# 1_Sheet_1.net
KiCad netlist of a schematic drawn in Altium Designer
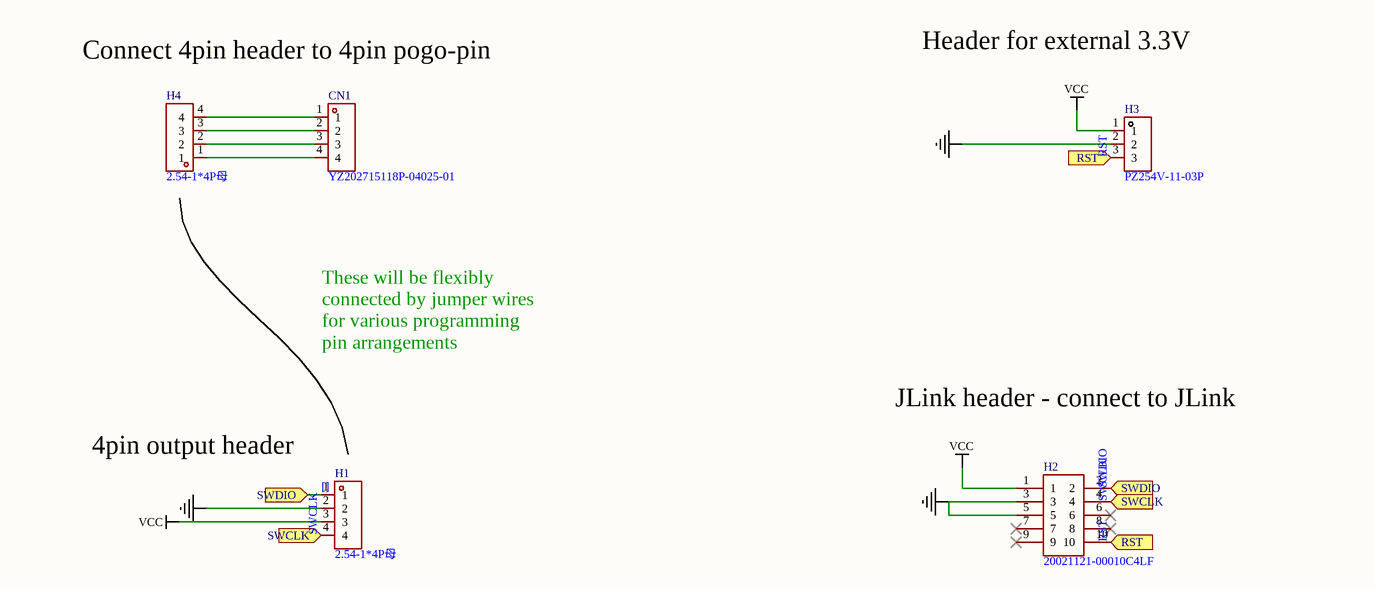
[diagram p0: 1_Sheet_1.schdoc]

(export (version "E")
  (design (tool "Eeschema 10.0.6"))
  (components
    (comp (ref "CN1")
      (value "YZ202715118P-04025-01")
      (footprint "BAT-TH_4P-P2.50_YZ202715118P-04025-01")
      (fields (field (name "MANUFACTURER") "Xinyangze(鑫扬泽)"))
      (libsource (lib "altium-import") (part "root_0_YZ202715118P-04025-01_"))
    )
    (comp (ref "H1")
      (value "2.54-1*4P母")
      (footprint "HDR-TH_4P-P2.54-V-F")
      (fields (field (name "MANUFACTURER") "BOOMELE(博穆精密)"))
      (libsource (lib "altium-import") (part "root_0_2.54-1*4P母_"))
    )
    (comp (ref "H2")
      (value "20021121-00010C4LF")
      (footprint "HDR-SMD_10P-P1.27-V-M-R2-C5-S1.27-LS5.5")
      (fields (field (name "MANUFACTURER") "Amphenol"))
      (libsource (lib "altium-import") (part "root_3_20021121-00010C4LF_"))
    )
    (comp (ref "H3")
      (value "PZ254V-11-03P")
      (footprint "HDR-TH_3P-P2.54-V-M")
      (fields (field (name "MANUFACTURER") "XFCN(兴飞)"))
      (libsource (lib "altium-import") (part "root_0_PZ254V-11-03P_"))
    )
    (comp (ref "H4")
      (value "2.54-1*4P母")
      (footprint "HDR-TH_4P-P2.54-V-F")
      (fields (field (name "MANUFACTURER") "BOOMELE(博穆精密)"))
      (libsource (lib "altium-import") (part "root_2_2.54-1*4P母_"))
    )
  )
  (nets
    (net (code "1") (name "/RST") (class "Default")
      (node (ref "H2") (pin "10") (pinfunction "10_10") (pintype "passive"))
      (node (ref "H3") (pin "3") (pinfunction "3_3") (pintype "passive"))
    )
    (net (code "2") (name "/SWCLK") (class "Default")
      (node (ref "H1") (pin "4") (pinfunction "4_4") (pintype "passive"))
      (node (ref "H2") (pin "4") (pinfunction "4_4") (pintype "passive"))
    )
    (net (code "3") (name "/SWDIO") (class "Default")
      (node (ref "H1") (pin "1") (pinfunction "1_1") (pintype "passive"))
      (node (ref "H2") (pin "2") (pinfunction "2_2") (pintype "passive"))
    )
    (net (code "4") (name "GND") (class "Default")
      (node (ref "H1") (pin "2") (pinfunction "2_2") (pintype "passive"))
      (node (ref "H2") (pin "3") (pinfunction "3_3") (pintype "passive"))
      (node (ref "H2") (pin "5") (pinfunction "5_5") (pintype "passive"))
      (node (ref "H3") (pin "2") (pinfunction "2_2") (pintype "passive"))
    )
    (net (code "5") (name "Net-(CN1-Pad1)") (class "Default")
      (node (ref "CN1") (pin "1") (pinfunction "1_1") (pintype "passive"))
      (node (ref "H4") (pin "4") (pinfunction "4_4") (pintype "passive"))
    )
    (net (code "6") (name "Net-(CN1-Pad2)") (class "Default")
      (node (ref "CN1") (pin "2") (pinfunction "2_2") (pintype "passive"))
      (node (ref "H4") (pin "3") (pinfunction "3_3") (pintype "passive"))
    )
    (net (code "7") (name "Net-(CN1-Pad3)") (class "Default")
      (node (ref "CN1") (pin "3") (pinfunction "3_3") (pintype "passive"))
      (node (ref "H4") (pin "2") (pinfunction "2_2") (pintype "passive"))
    )
    (net (code "8") (name "Net-(CN1-Pad4)") (class "Default")
      (node (ref "CN1") (pin "4") (pinfunction "4_4") (pintype "passive"))
      (node (ref "H4") (pin "1") (pinfunction "1_1") (pintype "passive"))
    )
    (net (code "9") (name "VCC") (class "Default")
      (node (ref "H1") (pin "3") (pinfunction "3_3") (pintype "passive"))
      (node (ref "H2") (pin "1") (pinfunction "1_1") (pintype "passive"))
      (node (ref "H3") (pin "1") (pinfunction "1_1") (pintype "passive"))
    )
    (net (code "10") (name "unconnected-(H2-Pad6)") (class "Default")
      (node (ref "H2") (pin "6") (pinfunction "6_6") (pintype "passive+no_connect"))
    )
    (net (code "11") (name "unconnected-(H2-Pad7)") (class "Default")
      (node (ref "H2") (pin "7") (pinfunction "7_7") (pintype "passive+no_connect"))
    )
    (net (code "12") (name "unconnected-(H2-Pad8)") (class "Default")
      (node (ref "H2") (pin "8") (pinfunction "8_8") (pintype "passive+no_connect"))
    )
    (net (code "13") (name "unconnected-(H2-Pad9)") (class "Default")
      (node (ref "H2") (pin "9") (pinfunction "9_9") (pintype "passive+no_connect"))
    )
  )
)
